# SwitchingPowerSupply.net
KiCad netlist of a schematic drawn in Altium Designer
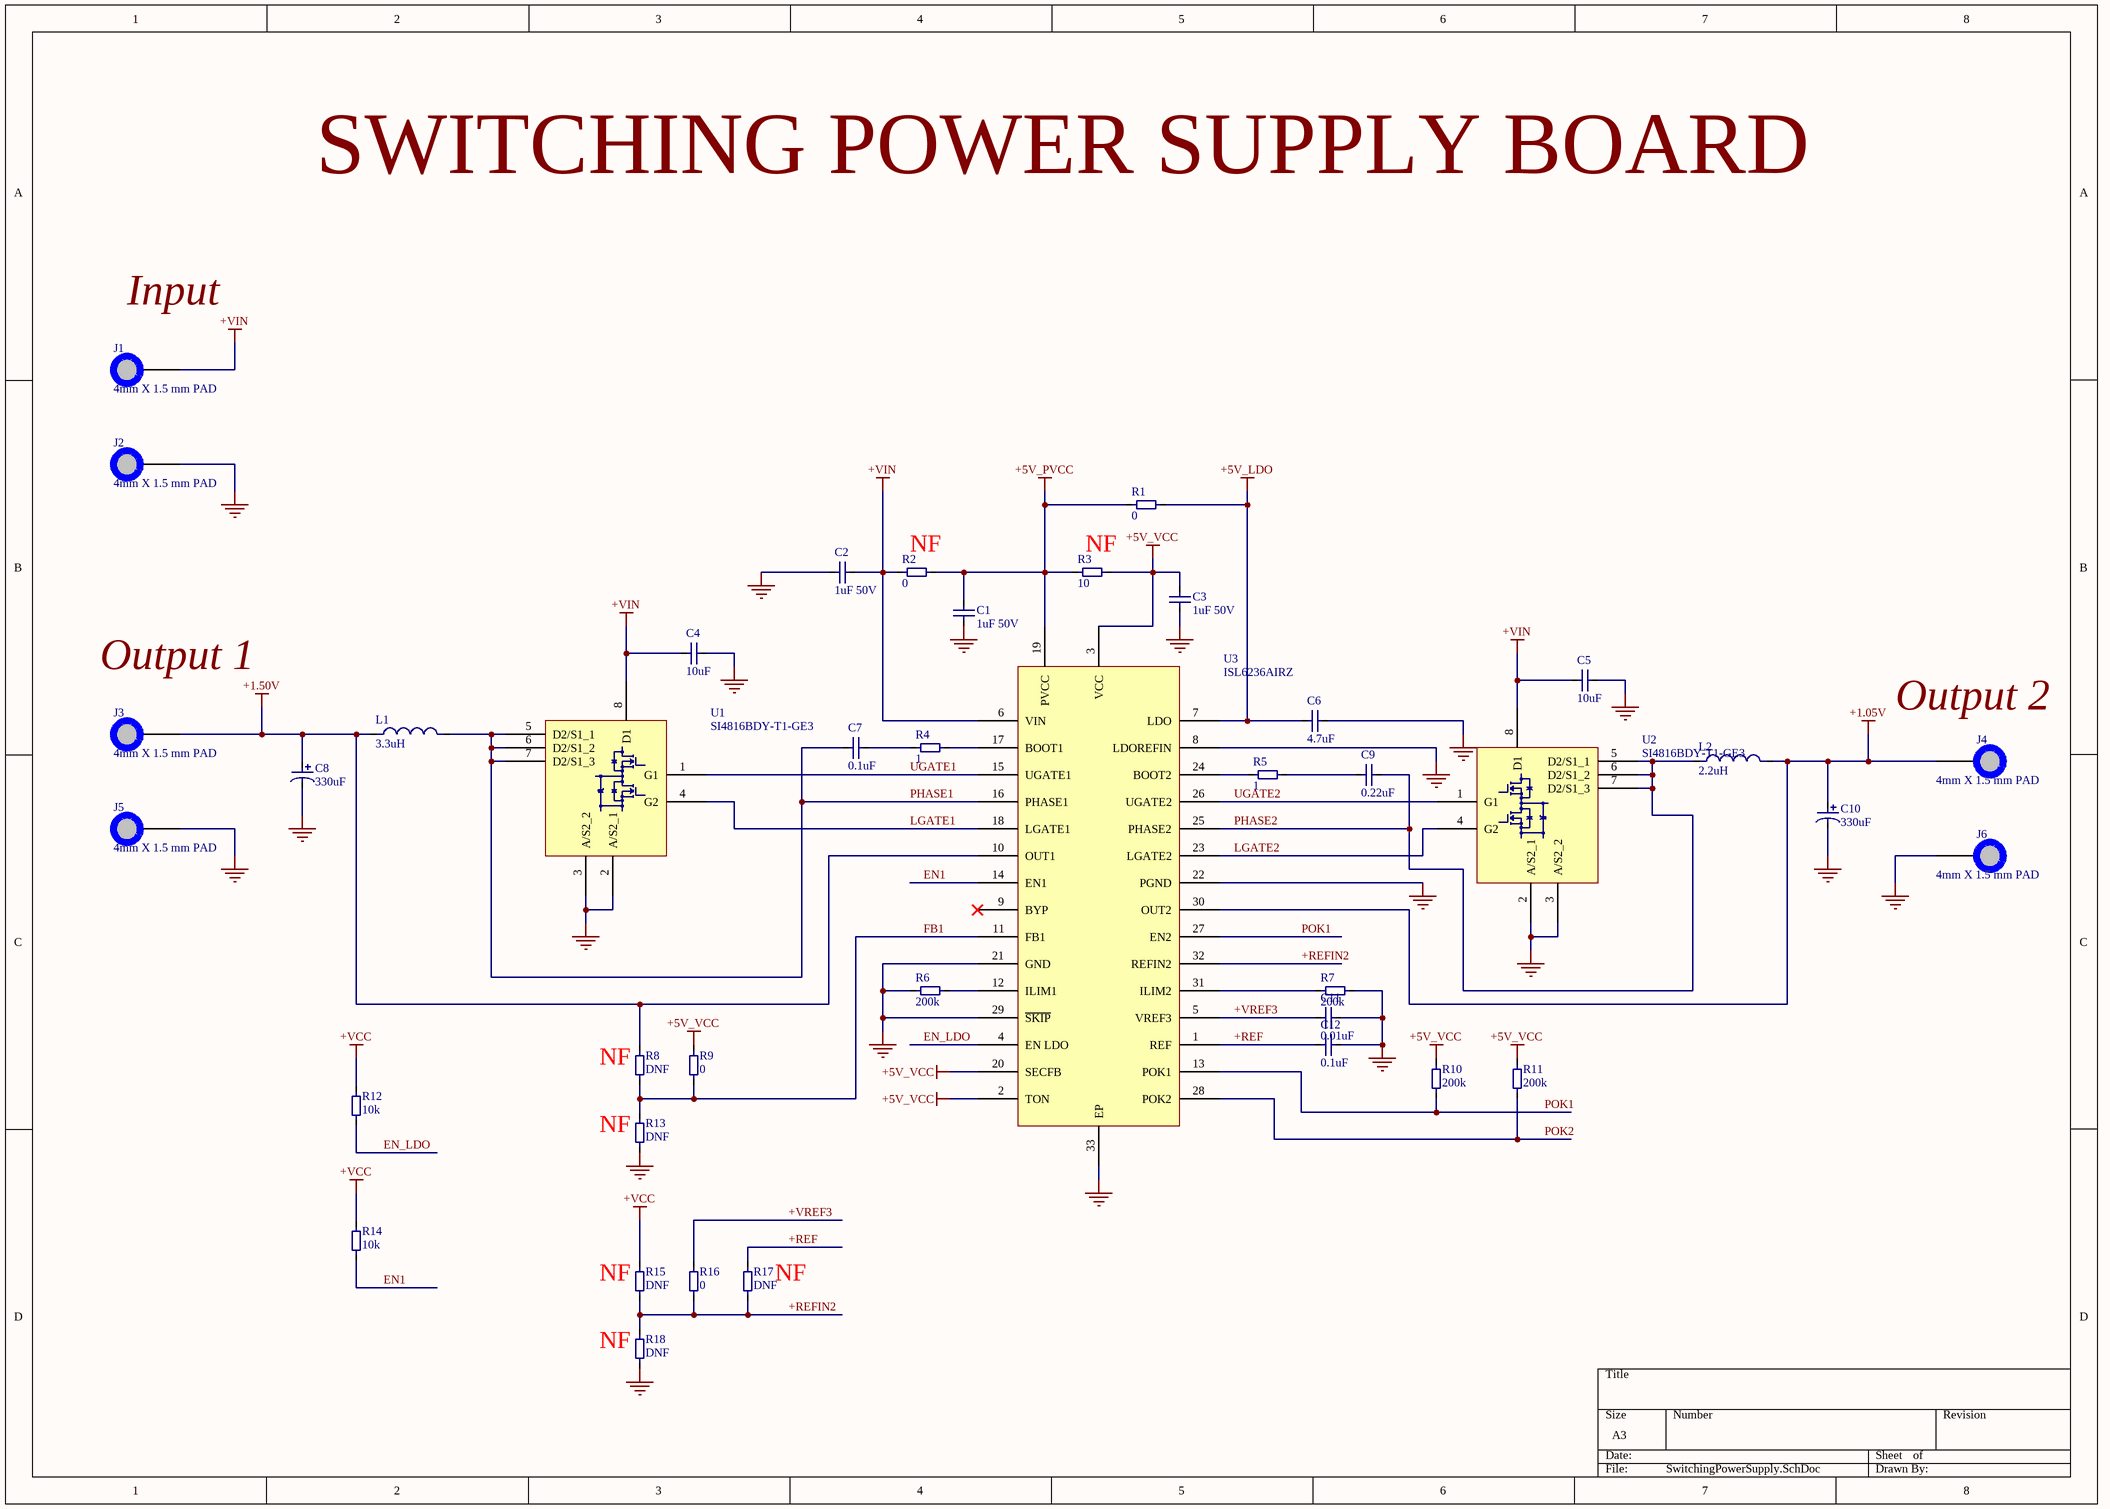
[diagram p0: SwitchingPowerSupply.SchDoc]

(export (version "E")
  (design (tool "Eeschema 10.0.6"))
  (components
    (comp (ref "C1")
      (value "1uF 50V")
      (footprint "C0805")
      (description "Multilayer Ceramic Capacitors MLCC - SMD/SMT CAP MLCC 0805 50V Y5V 1uF +80/-20%")
      (fields
        (field (name "MANUFACTURER") "Taiyo Yuden")
        (field (name "MANUFACTURER PART NUMBER") "UMK212F105ZG-T")
      )
      (libsource (lib "SwitchingPowerSupplyCourse_Symbols") (part "UMK212F105ZG-T"))
    )
    (comp (ref "C2")
      (value "1uF 50V")
      (footprint "C0805")
      (description "Multilayer Ceramic Capacitors MLCC - SMD/SMT CAP MLCC 0805 50V Y5V 1uF +80/-20%")
      (fields
        (field (name "MANUFACTURER") "Taiyo Yuden")
        (field (name "MANUFACTURER PART NUMBER") "UMK212F105ZG-T")
      )
      (libsource (lib "SwitchingPowerSupplyCourse_Symbols") (part "UMK212F105ZG-T"))
    )
    (comp (ref "C3")
      (value "1uF 50V")
      (footprint "C0805")
      (description "Multilayer Ceramic Capacitors MLCC - SMD/SMT CAP MLCC 0805 50V Y5V 1uF +80/-20%")
      (fields
        (field (name "MANUFACTURER") "Taiyo Yuden")
        (field (name "MANUFACTURER PART NUMBER") "UMK212F105ZG-T")
      )
      (libsource (lib "SwitchingPowerSupplyCourse_Symbols") (part "UMK212F105ZG-T"))
    )
    (comp (ref "C4")
      (value "10uF")
      (footprint "C1210")
      (description "Multilayer Ceramic Capacitors MLCC - SMD/SMT CAP MLCC 1210 50V X5R 10uF 20%")
      (fields
        (field (name "MANUFACTURER") "Taiyo Yuden")
        (field (name "MANUFACTURER PART NUMBER") "UMK325BJ106MM-T")
      )
      (libsource (lib "SwitchingPowerSupplyCourse_Symbols") (part "UMK325BJ106MM-T"))
    )
    (comp (ref "C5")
      (value "10uF")
      (footprint "C1210")
      (description "Multilayer Ceramic Capacitors MLCC - SMD/SMT CAP MLCC 1210 50V X5R 10uF 20%")
      (fields
        (field (name "MANUFACTURER") "Taiyo Yuden")
        (field (name "MANUFACTURER PART NUMBER") "UMK325BJ106MM-T")
      )
      (libsource (lib "SwitchingPowerSupplyCourse_Symbols") (part "UMK325BJ106MM-T"))
    )
    (comp (ref "C6")
      (value "4.7uF")
      (footprint "C1206")
      (description "Multilayer Ceramic Capacitors MLCC - SMD/SMT 1206 4.7uF 10volts X5R 10%")
      (fields (field (name "MANUFACTURER") "AVX") (field (name "MANUFACTURER PART NUMBER") "1206ZD475KAT2A"))
      (libsource (lib "SwitchingPowerSupplyCourse_Symbols") (part "1206ZD475KAT2A"))
    )
    (comp (ref "C7")
      (value "0.1uF")
      (footprint "C0805")
      (description "Multilayer Ceramic Capacitors MLCC - SMD/SMT 50volts 0.1uF 10%")
      (fields
        (field (name "MANUFACTURER") "Syfer")
        (field (name "MANUFACTURER PART NUMBER") "0805J0500104KJT")
      )
      (libsource (lib "SwitchingPowerSupplyCourse_Symbols") (part "0805J0500104KJT"))
    )
    (comp (ref "C8")
      (value "330uF")
      (footprint "7343-31")
      (description "Tantalum Capacitors - Solid SMD 10volts 330uF 10% ESR=150mOhms")
      (fields
        (field (name "MANUFACTURER") "Kemet")
        (field (name "MANUFACTURER PART NUMBER") "T495D337K010ATE150")
      )
      (libsource (lib "SwitchingPowerSupplyCourse_Symbols") (part "T495D337K010ATE150"))
    )
    (comp (ref "C9")
      (value "0.22uF")
      (footprint "C0805")
      (description "Multilayer Ceramic Capacitors MLCC - SMD/SMT CAP MLCC 0805 50V X7R 0.22uF 10%")
      (fields
        (field (name "MANUFACTURER") "Taiyo Yuden")
        (field (name "MANUFACTURER PART NUMBER") "UMK212B7224KG-T")
      )
      (libsource (lib "SwitchingPowerSupplyCourse_Symbols") (part "UMK212B7224KG-T"))
    )
    (comp (ref "C10")
      (value "330uF")
      (footprint "7343-31")
      (description "Tantalum Capacitors - Solid SMD 10volts 330uF 10% ESR=150mOhms")
      (fields
        (field (name "MANUFACTURER") "Kemet")
        (field (name "MANUFACTURER PART NUMBER") "T495D337K010ATE150")
      )
      (libsource (lib "SwitchingPowerSupplyCourse_Symbols") (part "T495D337K010ATE150"))
    )
    (comp (ref "C11")
      (value "0.01uF")
      (footprint "C0805")
      (description "Multilayer Ceramic Capacitors MLCC - SMD/SMT 0805 0.01uF 50volts X7R 5%")
      (fields
        (field (name "MANUFACTURER") "Vishay / Vitramon")
        (field (name "MANUFACTURER PART NUMBER") "VJ0805Y103JXAPW1BC")
      )
      (libsource (lib "SwitchingPowerSupplyCourse_Symbols") (part "VJ0805Y103JXAPW1BC"))
    )
    (comp (ref "C12")
      (value "0.1uF")
      (footprint "C0805")
      (description "Multilayer Ceramic Capacitors MLCC - SMD/SMT 50volts 0.1uF 10%")
      (fields
        (field (name "MANUFACTURER") "Syfer")
        (field (name "MANUFACTURER PART NUMBER") "0805J0500104KJT")
      )
      (libsource (lib "SwitchingPowerSupplyCourse_Symbols") (part "0805J0500104KJT"))
    )
    (comp (ref "J1")
      (value "4mm X 1.5 mm PAD")
      (footprint "PAD_WITH_HOLE_4mmX1.5mm")
      (description "Elliptical pad 4mm x 1.5 mm")
      (libsource (lib "SwitchingPowerSupplyCourse_Symbols") (part "4mmX1.5mm_PAD"))
    )
    (comp (ref "J2")
      (value "4mm X 1.5 mm PAD")
      (footprint "PAD_WITH_HOLE_4mmX1.5mm")
      (description "Elliptical pad 4mm x 1.5 mm")
      (libsource (lib "SwitchingPowerSupplyCourse_Symbols") (part "4mmX1.5mm_PAD"))
    )
    (comp (ref "J3")
      (value "4mm X 1.5 mm PAD")
      (footprint "PAD_WITH_HOLE_4mmX1.5mm")
      (description "Elliptical pad 4mm x 1.5 mm")
      (libsource (lib "SwitchingPowerSupplyCourse_Symbols") (part "4mmX1.5mm_PAD"))
    )
    (comp (ref "J4")
      (value "4mm X 1.5 mm PAD")
      (footprint "PAD_WITH_HOLE_4mmX1.5mm")
      (description "Elliptical pad 4mm x 1.5 mm")
      (libsource (lib "SwitchingPowerSupplyCourse_Symbols") (part "4mmX1.5mm_PAD"))
    )
    (comp (ref "J5")
      (value "4mm X 1.5 mm PAD")
      (footprint "PAD_WITH_HOLE_4mmX1.5mm")
      (description "Elliptical pad 4mm x 1.5 mm")
      (libsource (lib "SwitchingPowerSupplyCourse_Symbols") (part "4mmX1.5mm_PAD"))
    )
    (comp (ref "J6")
      (value "4mm X 1.5 mm PAD")
      (footprint "PAD_WITH_HOLE_4mmX1.5mm")
      (description "Elliptical pad 4mm x 1.5 mm")
      (libsource (lib "SwitchingPowerSupplyCourse_Symbols") (part "4mmX1.5mm_PAD"))
    )
    (comp (ref "L1")
      (value "3.3uH")
      (footprint "SRP1265A")
      (description "Fixed Inductors 3.3uH 20% SMD 1265")
      (fields
        (field (name "MANUFACTURER") "Bourns")
        (field (name "MANUFACTURER PART NUMBER") "SRP1265A-3R3M")
      )
      (libsource (lib "SwitchingPowerSupplyCourse_Symbols") (part "SRP1265A-3R3M"))
    )
    (comp (ref "L2")
      (value "2.2uH")
      (footprint "SRP1265A")
      (description "Fixed Inductors 2.2uH 20% SMD 1265")
      (fields
        (field (name "MANUFACTURER") "Bourns")
        (field (name "MANUFACTURER PART NUMBER") "SRP1265A-2R2M")
      )
      (libsource (lib "SwitchingPowerSupplyCourse_Symbols") (part "SRP1265A-2R2M"))
    )
    (comp (ref "R1")
      (value "0")
      (footprint "R0805")
      (description "Thick Film Resistors - SMD ZEROohms JUMPER")
      (fields
        (field (name "MANUFACTURER") "KOA Speer")
        (field (name "MANUFACTURER PART NUMBER") "RK73Z2ATTD")
      )
      (libsource (lib "SwitchingPowerSupplyCourse_Symbols") (part "RK73Z2ATTD"))
    )
    (comp (ref "R2")
      (value "0")
      (footprint "R0805")
      (description "Thick Film Resistors - SMD ZEROohms JUMPER")
      (fields
        (field (name "MANUFACTURER") "KOA Speer")
        (field (name "MANUFACTURER PART NUMBER") "RK73Z2ATTD")
      )
      (libsource (lib "SwitchingPowerSupplyCourse_Symbols") (part "RK73Z2ATTD"))
    )
    (comp (ref "R3")
      (value "10")
      (footprint "R0805")
      (description "Thick Film Resistors - SMD 1/8watt 10ohms 1% 100ppm")
      (fields
        (field (name "MANUFACTURER") "Vishay / Dale")
        (field (name "MANUFACTURER PART NUMBER") "CRCW080510R0FKEA")
      )
      (libsource (lib "SwitchingPowerSupplyCourse_Symbols") (part "CRCW080510R0FKEA"))
    )
    (comp (ref "R4")
      (value "1")
      (footprint "R0805")
      (description "Thick Film Resistors - SMD 1/8watt 1ohms 100ppm")
      (fields
        (field (name "MANUFACTURER") "Vishay / Dale")
        (field (name "MANUFACTURER PART NUMBER") "CRCW08051R00FKEA")
      )
      (libsource (lib "SwitchingPowerSupplyCourse_Symbols") (part "CRCW08051R00FKEA"))
    )
    (comp (ref "R5")
      (value "1")
      (footprint "R0805")
      (description "Thick Film Resistors - SMD 1/8watt 1ohms 100ppm")
      (fields
        (field (name "MANUFACTURER") "Vishay / Dale")
        (field (name "MANUFACTURER PART NUMBER") "CRCW08051R00FKEA")
      )
      (libsource (lib "SwitchingPowerSupplyCourse_Symbols") (part "CRCW08051R00FKEA"))
    )
    (comp (ref "R6")
      (value "200k")
      (footprint "R0805")
      (description "Thick Film Resistors - SMD 1/8watts 200Kohms 1%")
      (fields
        (field (name "MANUFACTURER") "KOA Speer")
        (field (name "MANUFACTURER PART NUMBER") "RK73H2ATTD2003F")
      )
      (libsource (lib "SwitchingPowerSupplyCourse_Symbols") (part "RK73H2ATTD2003F"))
    )
    (comp (ref "R7")
      (value "200k")
      (footprint "R0805")
      (description "Thick Film Resistors - SMD 1/8watts 200Kohms 1%")
      (fields
        (field (name "MANUFACTURER") "KOA Speer")
        (field (name "MANUFACTURER PART NUMBER") "RK73H2ATTD2003F")
      )
      (libsource (lib "SwitchingPowerSupplyCourse_Symbols") (part "RK73H2ATTD2003F"))
    )
    (comp (ref "R8")
      (value "DNF")
      (footprint "R0805")
      (description "Generic Do Not Fit Capacitor")
      (libsource (lib "SwitchingPowerSupplyCourse_Symbols") (part "RES"))
    )
    (comp (ref "R9")
      (value "0")
      (footprint "R0805")
      (description "Thick Film Resistors - SMD ZEROohms JUMPER")
      (fields
        (field (name "MANUFACTURER") "KOA Speer")
        (field (name "MANUFACTURER PART NUMBER") "RK73Z2ATTD")
      )
      (libsource (lib "SwitchingPowerSupplyCourse_Symbols") (part "RK73Z2ATTD"))
    )
    (comp (ref "R10")
      (value "200k")
      (footprint "R0805")
      (description "Thick Film Resistors - SMD 1/8watts 200Kohms 1%")
      (fields
        (field (name "MANUFACTURER") "KOA Speer")
        (field (name "MANUFACTURER PART NUMBER") "RK73H2ATTD2003F")
      )
      (libsource (lib "SwitchingPowerSupplyCourse_Symbols") (part "RK73H2ATTD2003F"))
    )
    (comp (ref "R11")
      (value "200k")
      (footprint "R0805")
      (description "Thick Film Resistors - SMD 1/8watts 200Kohms 1%")
      (fields
        (field (name "MANUFACTURER") "KOA Speer")
        (field (name "MANUFACTURER PART NUMBER") "RK73H2ATTD2003F")
      )
      (libsource (lib "SwitchingPowerSupplyCourse_Symbols") (part "RK73H2ATTD2003F"))
    )
    (comp (ref "R12")
      (value "10k")
      (footprint "R0805")
      (description "Thick Film Resistors - SMD 0.25W 10Kohm 1% 200ppm")
      (fields
        (field (name "MANUFACTURER") "KOA Speer")
        (field (name "MANUFACTURER PART NUMBER") "SG73P2ATTD1002F")
      )
      (libsource (lib "SwitchingPowerSupplyCourse_Symbols") (part "SG73P2ATTD1002F"))
    )
    (comp (ref "R13")
      (value "DNF")
      (footprint "R0805")
      (description "Generic Do Not Fit Capacitor")
      (libsource (lib "SwitchingPowerSupplyCourse_Symbols") (part "RES"))
    )
    (comp (ref "R14")
      (value "10k")
      (footprint "R0805")
      (description "Thick Film Resistors - SMD 0.25W 10Kohm 1% 200ppm")
      (fields
        (field (name "MANUFACTURER") "KOA Speer")
        (field (name "MANUFACTURER PART NUMBER") "SG73P2ATTD1002F")
      )
      (libsource (lib "SwitchingPowerSupplyCourse_Symbols") (part "SG73P2ATTD1002F"))
    )
    (comp (ref "R15")
      (value "DNF")
      (footprint "R0805")
      (description "Generic Do Not Fit Capacitor")
      (libsource (lib "SwitchingPowerSupplyCourse_Symbols") (part "RES"))
    )
    (comp (ref "R16")
      (value "0")
      (footprint "R0805")
      (description "Thick Film Resistors - SMD ZEROohms JUMPER")
      (fields
        (field (name "MANUFACTURER") "KOA Speer")
        (field (name "MANUFACTURER PART NUMBER") "RK73Z2ATTD")
      )
      (libsource (lib "SwitchingPowerSupplyCourse_Symbols") (part "RK73Z2ATTD"))
    )
    (comp (ref "R17")
      (value "DNF")
      (footprint "R0805")
      (description "Generic Do Not Fit Capacitor")
      (libsource (lib "SwitchingPowerSupplyCourse_Symbols") (part "RES"))
    )
    (comp (ref "R18")
      (value "DNF")
      (footprint "R0805")
      (description "Generic Do Not Fit Capacitor")
      (libsource (lib "SwitchingPowerSupplyCourse_Symbols") (part "RES"))
    )
    (comp (ref "U1")
      (value "SI4816BDY-T1-GE3")
      (footprint "SO-8")
      (description "MOSFET Dua lN-Ch w/Schottky 30V 18.5/11.5mohm")
      (fields (field (name "MANUFACTURER") "Vishay / Siliconix"))
      (libsource (lib "SwitchingPowerSupplyCourse_Symbols") (part "SI4816BDY-T1-GE3"))
    )
    (comp (ref "U2")
      (value "SI4816BDY-T1-GE3")
      (footprint "SO-8")
      (description "MOSFET Dua lN-Ch w/Schottky 30V 18.5/11.5mohm")
      (fields (field (name "MANUFACTURER") "Vishay / Siliconix"))
      (libsource (lib "SwitchingPowerSupplyCourse_Symbols") (part "SI4816BDY-T1-GE3"))
    )
    (comp (ref "U3")
      (value "ISL6236AIRZ")
      (footprint "L32.5x5B")
      (description "Switching Controllers ISL6236 QD QUTPUT CNTRLR IMVP-6 32LD")
      (fields (field (name "MANUFACTURER") "Intersil"))
      (libsource (lib "SwitchingPowerSupplyCourse_Symbols") (part "ISL6236AIRZ"))
    )
  )
  (nets
    (net (code "1") (name "+1.05V") (class "Default")
      (node (ref "C10") (pin "1") (pinfunction "1_1") (pintype "passive"))
      (node (ref "J4") (pin "1") (pinfunction "1_1") (pintype "passive"))
      (node (ref "L2") (pin "2") (pinfunction "2_2") (pintype "passive"))
      (node (ref "U3") (pin "30") (pinfunction "OUT2_30") (pintype "passive"))
    )
    (net (code "2") (name "+1.50V") (class "Default")
      (node (ref "C8") (pin "1") (pinfunction "1_1") (pintype "passive"))
      (node (ref "J3") (pin "1") (pinfunction "1_1") (pintype "passive"))
      (node (ref "L1") (pin "1") (pinfunction "1_1") (pintype "passive"))
      (node (ref "R8") (pin "2") (pinfunction "2_2") (pintype "passive"))
      (node (ref "U3") (pin "10") (pinfunction "OUT1_10") (pintype "passive"))
    )
    (net (code "3") (name "+5V_LDO") (class "Default")
      (node (ref "C6") (pin "2") (pinfunction "2_2") (pintype "passive"))
      (node (ref "R1") (pin "2") (pinfunction "2_2") (pintype "passive"))
      (node (ref "U3") (pin "7") (pinfunction "LDO_7") (pintype "passive"))
    )
    (net (code "4") (name "+5V_PVCC") (class "Default")
      (node (ref "C1") (pin "2") (pinfunction "2_2") (pintype "passive"))
      (node (ref "R1") (pin "1") (pinfunction "1_1") (pintype "passive"))
      (node (ref "R2") (pin "2") (pinfunction "2_2") (pintype "passive"))
      (node (ref "R3") (pin "1") (pinfunction "1_1") (pintype "passive"))
      (node (ref "U3") (pin "19") (pinfunction "PVCC_19") (pintype "passive"))
    )
    (net (code "5") (name "+5V_VCC") (class "Default")
      (node (ref "C3") (pin "1") (pinfunction "1_1") (pintype "passive"))
      (node (ref "R10") (pin "1") (pinfunction "1_1") (pintype "passive"))
      (node (ref "R11") (pin "1") (pinfunction "1_1") (pintype "passive"))
      (node (ref "R3") (pin "2") (pinfunction "2_2") (pintype "passive"))
      (node (ref "R9") (pin "2") (pinfunction "2_2") (pintype "passive"))
      (node (ref "U3") (pin "2") (pinfunction "TON_2") (pintype "passive"))
      (node (ref "U3") (pin "20") (pinfunction "SECFB_20") (pintype "passive"))
      (node (ref "U3") (pin "3") (pinfunction "VCC_3") (pintype "passive"))
    )
    (net (code "6") (name "+VCC") (class "Default")
      (node (ref "R12") (pin "2") (pinfunction "2_2") (pintype "passive"))
      (node (ref "R14") (pin "2") (pinfunction "2_2") (pintype "passive"))
      (node (ref "R15") (pin "2") (pinfunction "2_2") (pintype "passive"))
    )
    (net (code "7") (name "+VIN") (class "Default")
      (node (ref "C2") (pin "2") (pinfunction "2_2") (pintype "passive"))
      (node (ref "C4") (pin "1") (pinfunction "1_1") (pintype "passive"))
      (node (ref "C5") (pin "1") (pinfunction "1_1") (pintype "passive"))
      (node (ref "J1") (pin "1") (pinfunction "1_1") (pintype "passive"))
      (node (ref "R2") (pin "1") (pinfunction "1_1") (pintype "passive"))
      (node (ref "U1") (pin "8") (pinfunction "D1_8") (pintype "passive"))
      (node (ref "U2") (pin "8") (pinfunction "D1_8") (pintype "passive"))
      (node (ref "U3") (pin "6") (pinfunction "VIN_6") (pintype "passive"))
    )
    (net (code "8") (name "/+REF") (class "Default")
      (node (ref "C12") (pin "1") (pinfunction "1_1") (pintype "passive"))
      (node (ref "R17") (pin "2") (pinfunction "2_2") (pintype "passive"))
      (node (ref "U3") (pin "1") (pinfunction "REF_1") (pintype "passive"))
    )
    (net (code "9") (name "/+REFIN2") (class "Default")
      (node (ref "R15") (pin "1") (pinfunction "1_1") (pintype "passive"))
      (node (ref "R16") (pin "1") (pinfunction "1_1") (pintype "passive"))
      (node (ref "R17") (pin "1") (pinfunction "1_1") (pintype "passive"))
      (node (ref "R18") (pin "2") (pinfunction "2_2") (pintype "passive"))
      (node (ref "U3") (pin "32") (pinfunction "REFIN2_32") (pintype "passive"))
    )
    (net (code "10") (name "/+VREF3") (class "Default")
      (node (ref "C11") (pin "1") (pinfunction "1_1") (pintype "passive"))
      (node (ref "R16") (pin "2") (pinfunction "2_2") (pintype "passive"))
      (node (ref "U3") (pin "5") (pinfunction "VREF3_5") (pintype "passive"))
    )
    (net (code "11") (name "/EN1") (class "Default")
      (node (ref "R14") (pin "1") (pinfunction "1_1") (pintype "passive"))
      (node (ref "U3") (pin "14") (pinfunction "EN1_14") (pintype "passive"))
    )
    (net (code "12") (name "/EN_LDO") (class "Default")
      (node (ref "R12") (pin "1") (pinfunction "1_1") (pintype "passive"))
      (node (ref "U3") (pin "4") (pinfunction "EN_LDO_4") (pintype "passive"))
    )
    (net (code "13") (name "/FB1") (class "Default")
      (node (ref "R13") (pin "2") (pinfunction "2_2") (pintype "passive"))
      (node (ref "R8") (pin "1") (pinfunction "1_1") (pintype "passive"))
      (node (ref "R9") (pin "1") (pinfunction "1_1") (pintype "passive"))
      (node (ref "U3") (pin "11") (pinfunction "FB1_11") (pintype "passive"))
    )
    (net (code "14") (name "/LGATE1") (class "Default")
      (node (ref "U1") (pin "4") (pinfunction "G2_4") (pintype "passive"))
      (node (ref "U3") (pin "18") (pinfunction "LGATE1_18") (pintype "passive"))
    )
    (net (code "15") (name "/LGATE2") (class "Default")
      (node (ref "U2") (pin "4") (pinfunction "G2_4") (pintype "passive"))
      (node (ref "U3") (pin "23") (pinfunction "LGATE2_23") (pintype "passive"))
    )
    (net (code "16") (name "/PHASE1") (class "Default")
      (node (ref "C7") (pin "1") (pinfunction "1_1") (pintype "passive"))
      (node (ref "L1") (pin "2") (pinfunction "2_2") (pintype "passive"))
      (node (ref "U1") (pin "5") (pinfunction "D2/S1_1_5") (pintype "passive"))
      (node (ref "U1") (pin "6") (pinfunction "D2/S1_2_6") (pintype "passive"))
      (node (ref "U1") (pin "7") (pinfunction "D2/S1_3_7") (pintype "passive"))
      (node (ref "U3") (pin "16") (pinfunction "PHASE1_16") (pintype "passive"))
    )
    (net (code "17") (name "/PHASE2") (class "Default")
      (node (ref "C9") (pin "2") (pinfunction "2_2") (pintype "passive"))
      (node (ref "L2") (pin "1") (pinfunction "1_1") (pintype "passive"))
      (node (ref "U2") (pin "5") (pinfunction "D2/S1_1_5") (pintype "passive"))
      (node (ref "U2") (pin "6") (pinfunction "D2/S1_2_6") (pintype "passive"))
      (node (ref "U2") (pin "7") (pinfunction "D2/S1_3_7") (pintype "passive"))
      (node (ref "U3") (pin "25") (pinfunction "PHASE2_25") (pintype "passive"))
    )
    (net (code "18") (name "/POK1") (class "Default")
      (node (ref "R10") (pin "2") (pinfunction "2_2") (pintype "passive"))
      (node (ref "U3") (pin "13") (pinfunction "POK1_13") (pintype "passive"))
      (node (ref "U3") (pin "27") (pinfunction "EN2_27") (pintype "passive"))
    )
    (net (code "19") (name "/POK2") (class "Default")
      (node (ref "R11") (pin "2") (pinfunction "2_2") (pintype "passive"))
      (node (ref "U3") (pin "28") (pinfunction "POK2_28") (pintype "passive"))
    )
    (net (code "20") (name "/UGATE1") (class "Default")
      (node (ref "U1") (pin "1") (pinfunction "G1_1") (pintype "passive"))
      (node (ref "U3") (pin "15") (pinfunction "UGATE1_15") (pintype "passive"))
    )
    (net (code "21") (name "/UGATE2") (class "Default")
      (node (ref "U2") (pin "1") (pinfunction "G1_1") (pintype "passive"))
      (node (ref "U3") (pin "26") (pinfunction "UGATE2_26") (pintype "passive"))
    )
    (net (code "22") (name "GND") (class "Default")
      (node (ref "C1") (pin "1") (pinfunction "1_1") (pintype "passive"))
      (node (ref "C10") (pin "2") (pinfunction "2_2") (pintype "passive"))
      (node (ref "C11") (pin "2") (pinfunction "2_2") (pintype "passive"))
      (node (ref "C12") (pin "2") (pinfunction "2_2") (pintype "passive"))
      (node (ref "C2") (pin "1") (pinfunction "1_1") (pintype "passive"))
      (node (ref "C3") (pin "2") (pinfunction "2_2") (pintype "passive"))
      (node (ref "C4") (pin "2") (pinfunction "2_2") (pintype "passive"))
      (node (ref "C5") (pin "2") (pinfunction "2_2") (pintype "passive"))
      (node (ref "C6") (pin "1") (pinfunction "1_1") (pintype "passive"))
      (node (ref "C8") (pin "2") (pinfunction "2_2") (pintype "passive"))
      (node (ref "J2") (pin "1") (pinfunction "1_1") (pintype "passive"))
      (node (ref "J5") (pin "1") (pinfunction "1_1") (pintype "passive"))
      (node (ref "J6") (pin "1") (pinfunction "1_1") (pintype "passive"))
      (node (ref "R13") (pin "1") (pinfunction "1_1") (pintype "passive"))
      (node (ref "R18") (pin "1") (pinfunction "1_1") (pintype "passive"))
      (node (ref "R6") (pin "1") (pinfunction "1_1") (pintype "passive"))
      (node (ref "R7") (pin "2") (pinfunction "2_2") (pintype "passive"))
      (node (ref "U1") (pin "2") (pinfunction "A/S2_1_2") (pintype "passive"))
      (node (ref "U1") (pin "3") (pinfunction "A/S2_2_3") (pintype "passive"))
      (node (ref "U2") (pin "2") (pinfunction "A/S2_1_2") (pintype "passive"))
      (node (ref "U2") (pin "3") (pinfunction "A/S2_2_3") (pintype "passive"))
      (node (ref "U3") (pin "21") (pinfunction "GND_21") (pintype "passive"))
      (node (ref "U3") (pin "22") (pinfunction "PGND_22") (pintype "passive"))
      (node (ref "U3") (pin "29") (pinfunction "~{SKIP}_29") (pintype "passive"))
      (node (ref "U3") (pin "33") (pinfunction "EP_33") (pintype "passive"))
      (node (ref "U3") (pin "8") (pinfunction "LDOREFIN_8") (pintype "passive"))
    )
    (net (code "23") (name "Net-(C7-Pad2)") (class "Default")
      (node (ref "C7") (pin "2") (pinfunction "2_2") (pintype "passive"))
      (node (ref "R4") (pin "1") (pinfunction "1_1") (pintype "passive"))
    )
    (net (code "24") (name "Net-(C9-Pad1)") (class "Default")
      (node (ref "C9") (pin "1") (pinfunction "1_1") (pintype "passive"))
      (node (ref "R5") (pin "2") (pinfunction "2_2") (pintype "passive"))
    )
    (net (code "25") (name "Net-(U3-BOOT1)") (class "Default")
      (node (ref "R4") (pin "2") (pinfunction "2_2") (pintype "passive"))
      (node (ref "U3") (pin "17") (pinfunction "BOOT1_17") (pintype "passive"))
    )
    (net (code "26") (name "Net-(U3-BOOT2)") (class "Default")
      (node (ref "R5") (pin "1") (pinfunction "1_1") (pintype "passive"))
      (node (ref "U3") (pin "24") (pinfunction "BOOT2_24") (pintype "passive"))
    )
    (net (code "27") (name "Net-(U3-ILIM1)") (class "Default")
      (node (ref "R6") (pin "2") (pinfunction "2_2") (pintype "passive"))
      (node (ref "U3") (pin "12") (pinfunction "ILIM1_12") (pintype "passive"))
    )
    (net (code "28") (name "Net-(U3-ILIM2)") (class "Default")
      (node (ref "R7") (pin "1") (pinfunction "1_1") (pintype "passive"))
      (node (ref "U3") (pin "31") (pinfunction "ILIM2_31") (pintype "passive"))
    )
    (net (code "29") (name "unconnected-(U3-BYP-Pad9)") (class "Default")
      (node (ref "U3") (pin "9") (pinfunction "BYP_9") (pintype "passive+no_connect"))
    )
  )
)
